# uInverter.net
KiCad netlist of a schematic drawn in Altium Designer
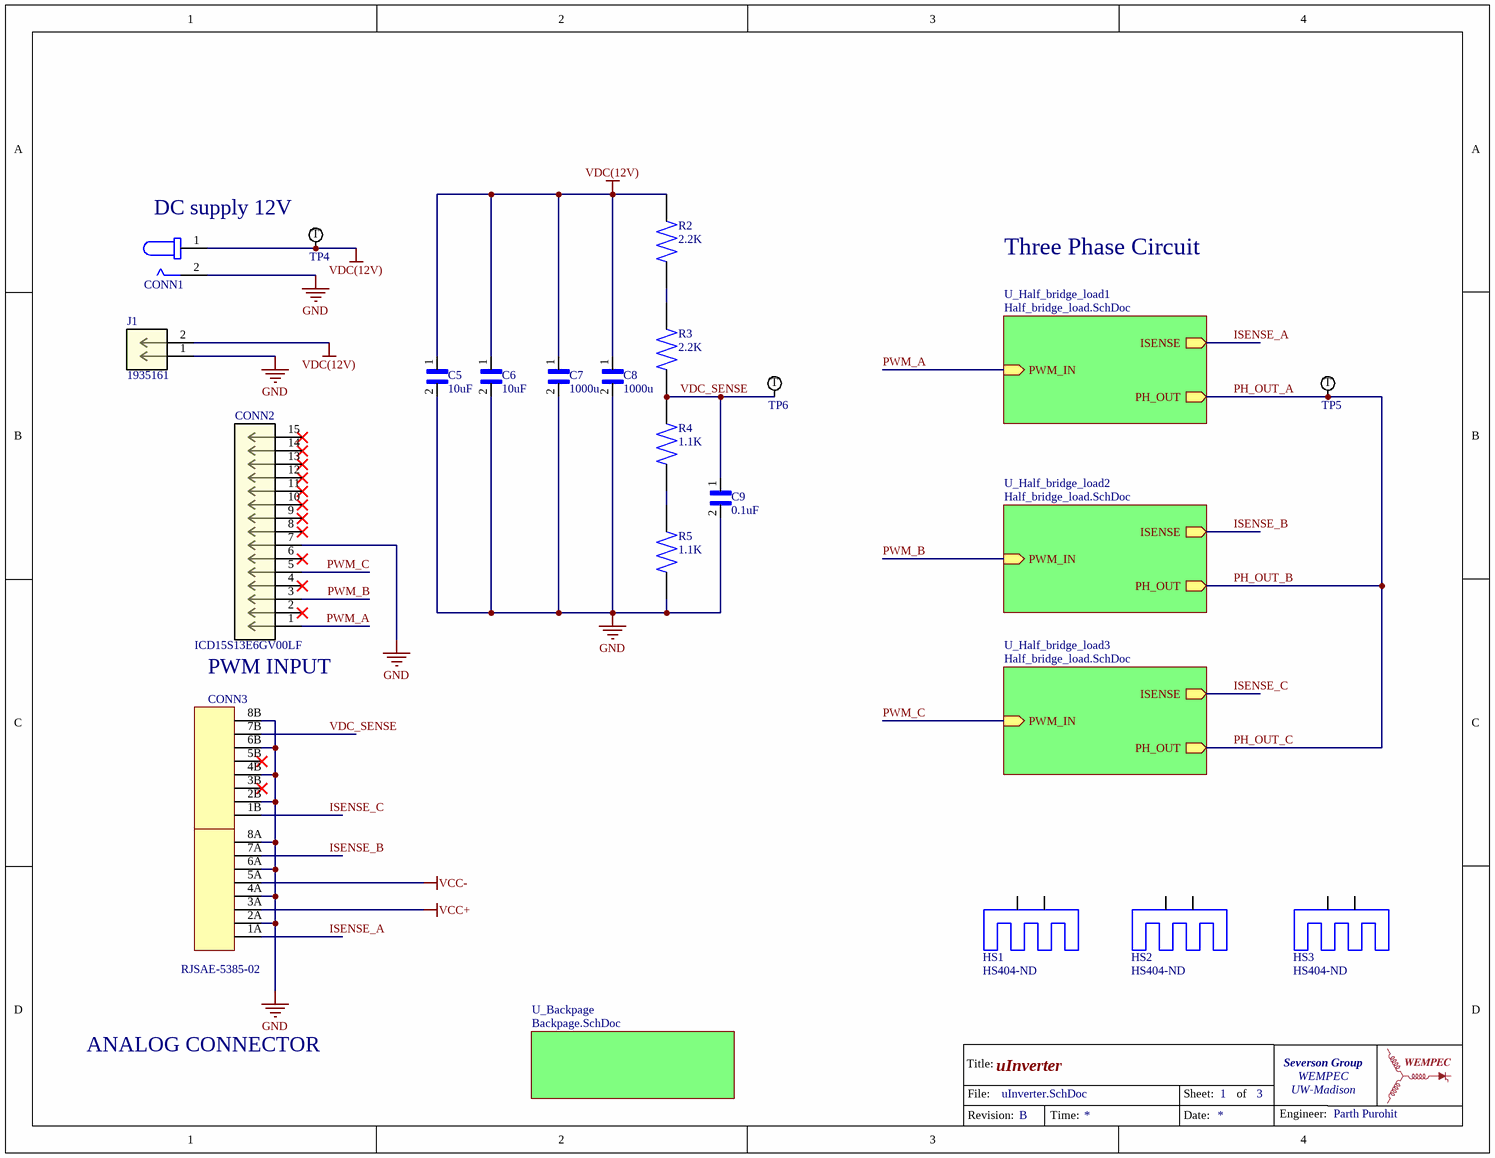
[diagram p0: uInverter.SchDoc]

(export (version "E")
  (design (tool "Eeschema 10.0.6"))
  (components
    (comp (ref "C5")
      (value "10uF")
      (footprint "PcbLib_uInverter:0805_CAP")
      (description "0805 35 V 10 uF ±10% Tolerance X5R Multilayer Ceramic Capacitor")
      (fields
        (field (name "MANUFACTURER") "Murata")
        (field (name "MANUFACTURER PART NUMBER") "GRM21BR6YA106KE43L")
      )
      (libsource (lib "Schlib_uInverter") (part "GRM21BR6YA106KE43L"))
    )
    (comp (ref "C6")
      (value "10uF")
      (footprint "PcbLib_uInverter:0805_CAP")
      (description "0805 35 V 10 uF ±10% Tolerance X5R Multilayer Ceramic Capacitor")
      (fields
        (field (name "MANUFACTURER") "Murata")
        (field (name "MANUFACTURER PART NUMBER") "GRM21BR6YA106KE43L")
      )
      (libsource (lib "Schlib_uInverter") (part "GRM21BR6YA106KE43L"))
    )
    (comp (ref "C7")
      (value "1000u")
      (footprint "CAP_PAN_12.5X25_PAN")
      (description "Cap Aluminum 1000uF 35V 20% (12.5 X 25mm) Radial 5mm 3190mA 7000 hr 105C Ammo Pack")
      (fields
        (field (name "MANUFACTURER") "Panasonic")
        (field (name "MANUFACTURER PART NUMBER") "EEU-FM1V102B")
      )
      (libsource (lib "Schlib_uInverter") (part "EEU-FM1V102B"))
    )
    (comp (ref "C8")
      (value "1000u")
      (footprint "CAP_PAN_12.5X25_PAN")
      (description "Cap Aluminum 1000uF 35V 20% (12.5 X 25mm) Radial 5mm 3190mA 7000 hr 105C Ammo Pack")
      (fields
        (field (name "MANUFACTURER") "Panasonic")
        (field (name "MANUFACTURER PART NUMBER") "EEU-FM1V102B")
      )
      (libsource (lib "Schlib_uInverter") (part "EEU-FM1V102B"))
    )
    (comp (ref "C9")
      (value "0.1uF")
      (footprint "PcbLib_uInverter:0805_CAP")
      (description "Capacitor 0.1uF 16V 0805 SMD X7R")
      (fields
        (field (name "MANUFACTURER") "Yageo")
        (field (name "MANUFACTURER PART NUMBER") "CC0805KRX7R7BB104")
      )
      (libsource (lib "Schlib_uInverter") (part "CC0805KRX7R7BB104"))
    )
    (comp (ref "CONN1")
      (value "PJ-037AH")
      (footprint "CUI_PJ-037AH")
      (description "CONN PWR JACK 2X5.5MM SOLDER")
      (fields (field (name "MANUFACTURER") "CUI"))
      (libsource (lib "Schlib_uInv01") (part "PJ-037AH"))
    )
    (comp (ref "CONN2")
      (value "ICD15S13E6GV00LF")
      (footprint "ICD15S13E6GV00LF")
      (description "Conn High Density D-Sub SKT 15 POS 2.28mm Solder RA Thru-Hole 15 Terminal 1 Port")
      (fields (field (name "MANUFACTURER") "Amphenol FCI"))
      (libsource (lib "Schlib_uInv01") (part "ICD15S13E6GV00LF"))
    )
    (comp (ref "CONN3")
      (value "RJSAE-5385-02")
      (footprint "CONN_RJSAE538502_AMP")
      (description "CONN MOD JACK 8P8C R/A SHIELDED")
      (fields (field (name "MANUFACTURER") "Amphenol Commercial"))
      (libsource (lib "Schlib_uInv01") (part "RJSAE-5385-02"))
    )
    (comp (ref "HS1")
      (value "529702B02500G")
      (footprint "530002")
      (description "Heat Sink Passive TO-220 Radial Thru-Hole 2.6C/W Black Anodized")
      (fields
        (field (name "MP") "530002B02500G")
        (field (name "MF") "Aavid Thermalloy")
        (field (name "SUPPLIER PART NUMBER 1") "HS404-ND")
      )
      (libsource (lib "Schlib_uInverter") (part "529702B02500G"))
    )
    (comp (ref "HS2")
      (value "529702B02500G")
      (footprint "530002")
      (description "Heat Sink Passive TO-220 Radial Thru-Hole 2.6C/W Black Anodized")
      (fields
        (field (name "MP") "530002B02500G")
        (field (name "MF") "Aavid Thermalloy")
        (field (name "SUPPLIER PART NUMBER 1") "HS404-ND")
      )
      (libsource (lib "Schlib_uInverter") (part "529702B02500G"))
    )
    (comp (ref "HS3")
      (value "529702B02500G")
      (footprint "530002")
      (description "Heat Sink Passive TO-220 Radial Thru-Hole 2.6C/W Black Anodized")
      (fields
        (field (name "MP") "530002B02500G")
        (field (name "MF") "Aavid Thermalloy")
        (field (name "SUPPLIER PART NUMBER 1") "HS404-ND")
      )
      (libsource (lib "Schlib_uInverter") (part "529702B02500G"))
    )
    (comp (ref "J1")
      (value "1935161")
      (footprint "PHOENIX_1935161")
      (description "Conn Terminal Blocks 2 POS 5mm Solder ST Thru-Hole 16A")
      (fields (field (name "MANUFACTURER") "Phoenix Contact") (field (name "VOLTAGE") "300V"))
      (libsource (lib "Schlib_uInv01") (part "1935161"))
    )
    (comp (ref "R2")
      (value "2.2K")
      (footprint "PcbLib_uInverter:0805_RES")
      (description "Res Thick Film 0805 2.2K Ohm 1% 0.4W")
      (fields
        (field (name "MANUFACTURER") "Vishay Dale")
        (field (name "MANUFACTURER PART NUMBER") "RCS08052K20FKEA")
      )
      (libsource (lib "Schlib_uInverter") (part "RCS08052K20FKEA"))
    )
    (comp (ref "R3")
      (value "2.2K")
      (footprint "PcbLib_uInverter:0805_RES")
      (description "Res Thick Film 0805 2.2K Ohm 1% 0.4W")
      (fields
        (field (name "MANUFACTURER") "Vishay Dale")
        (field (name "MANUFACTURER PART NUMBER") "RCS08052K20FKEA")
      )
      (libsource (lib "Schlib_uInverter") (part "RCS08052K20FKEA"))
    )
    (comp (ref "R4")
      (value "1.1K")
      (footprint "PcbLib_uInverter:0805_RES")
      (description "Res Thick Film 0805 1.1K Ohm 1% 0.4W")
      (fields (field (name "MANUFACTURER") "Rohm") (field (name "MANUFACTURER PART NUMBER") "ESR10EZPF1101"))
      (libsource (lib "Schlib_uInverter") (part "ESR10EZPF1101"))
    )
    (comp (ref "R5")
      (value "1.1K")
      (footprint "PcbLib_uInverter:0805_RES")
      (description "Res Thick Film 0805 1.1K Ohm 1% 0.4W")
      (fields (field (name "MANUFACTURER") "Rohm") (field (name "MANUFACTURER PART NUMBER") "ESR10EZPF1101"))
      (libsource (lib "Schlib_uInverter") (part "ESR10EZPF1101"))
    )
    (comp (ref "TitleBlockWEMPEC1")
      (value "TitleBlockWEMPEC")
      (libsource (lib "Schlib_uInv01") (part "TitleBlockWEMPEC"))
    )
    (comp (ref "TP4")
      (value "Test Point")
      (footprint "TP_1.6MM")
      (description "Conn Test Point SKT 1 POS ST Thru-Hole 1 Port")
      (fields
        (field (name "MANUFACTURER") "Keystone Electronics")
        (field (name "MANUFACTURER PART NUMBER") "5005")
      )
      (libsource (lib "Schlib_uInverter") (part "Test Point 36-5005ND"))
    )
    (comp (ref "TP5")
      (value "Test Point")
      (footprint "TP_1.6MM")
      (description "Conn Test Point SKT 1 POS ST Thru-Hole 1 Port")
      (fields
        (field (name "MANUFACTURER") "Keystone Electronics")
        (field (name "MANUFACTURER PART NUMBER") "5005")
      )
      (libsource (lib "Schlib_uInverter") (part "Test Point 36-5005ND"))
    )
    (comp (ref "TP6")
      (value "Test Point")
      (footprint "TP_1.6MM")
      (description "Conn Test Point SKT 1 POS ST Thru-Hole 1 Port")
      (fields
        (field (name "MANUFACTURER") "Keystone Electronics")
        (field (name "MANUFACTURER PART NUMBER") "5005")
      )
      (libsource (lib "Schlib_uInverter") (part "Test Point 36-5005ND"))
    )
  )
  (nets
    (net (code "1") (name "/ISENSE_A") (class "Default")
      (node (ref "CONN3") (pin "1A") (pinfunction "79_1A") (pintype "passive"))
    )
    (net (code "2") (name "/ISENSE_B") (class "Default")
      (node (ref "CONN3") (pin "7A") (pinfunction "79_7A") (pintype "passive"))
    )
    (net (code "3") (name "/ISENSE_C") (class "Default")
      (node (ref "CONN3") (pin "1B") (pinfunction "79_1B") (pintype "passive"))
    )
    (net (code "4") (name "/PH_OUT_A") (class "Default")
      (node (ref "TP5") (pin "1") (pinfunction "1_1") (pintype "passive"))
    )
    (net (code "5") (name "/PWM_A") (class "Default")
      (node (ref "CONN2") (pin "1") (pinfunction "1_1") (pintype "passive"))
    )
    (net (code "6") (name "/PWM_B") (class "Default")
      (node (ref "CONN2") (pin "3") (pinfunction "3_3") (pintype "passive"))
    )
    (net (code "7") (name "/PWM_C") (class "Default")
      (node (ref "CONN2") (pin "5") (pinfunction "5_5") (pintype "passive"))
    )
    (net (code "8") (name "/VDC_SENSE") (class "Default")
      (node (ref "C9") (pin "1") (pinfunction "1_1") (pintype "passive"))
      (node (ref "CONN3") (pin "7B") (pinfunction "79_7B") (pintype "passive"))
      (node (ref "R3") (pin "1") (pinfunction "1_1") (pintype "passive"))
      (node (ref "R4") (pin "2") (pinfunction "2_2") (pintype "passive"))
      (node (ref "TP6") (pin "1") (pinfunction "1_1") (pintype "passive"))
    )
    (net (code "9") (name "GND") (class "Default")
      (node (ref "C5") (pin "2") (pinfunction "2_2") (pintype "passive"))
      (node (ref "C6") (pin "2") (pinfunction "2_2") (pintype "passive"))
      (node (ref "C7") (pin "2") (pinfunction "2_2") (pintype "passive"))
      (node (ref "C8") (pin "2") (pinfunction "2_2") (pintype "passive"))
      (node (ref "C9") (pin "2") (pinfunction "2_2") (pintype "passive"))
      (node (ref "CONN1") (pin "2") (pinfunction "2_2") (pintype "passive"))
      (node (ref "CONN2") (pin "7") (pinfunction "7_7") (pintype "passive"))
      (node (ref "CONN3") (pin "2A") (pinfunction "79_2A") (pintype "passive"))
      (node (ref "CONN3") (pin "2B") (pinfunction "79_2B") (pintype "passive"))
      (node (ref "CONN3") (pin "4A") (pinfunction "79_4A") (pintype "passive"))
      (node (ref "CONN3") (pin "4B") (pinfunction "79_4B") (pintype "passive"))
      (node (ref "CONN3") (pin "6A") (pinfunction "79_6A") (pintype "passive"))
      (node (ref "CONN3") (pin "6B") (pinfunction "79_6B") (pintype "passive"))
      (node (ref "CONN3") (pin "8A") (pinfunction "79_8A") (pintype "passive"))
      (node (ref "CONN3") (pin "8B") (pinfunction "79_8B") (pintype "passive"))
      (node (ref "J1") (pin "1") (pinfunction "1_1") (pintype "passive"))
      (node (ref "R5") (pin "1") (pinfunction "1_1") (pintype "passive"))
    )
    (net (code "10") (name "Net-(R2-Pad1)") (class "Default")
      (node (ref "R2") (pin "1") (pinfunction "1_1") (pintype "passive"))
      (node (ref "R3") (pin "2") (pinfunction "2_2") (pintype "passive"))
    )
    (net (code "11") (name "Net-(R4-Pad1)") (class "Default")
      (node (ref "R4") (pin "1") (pinfunction "1_1") (pintype "passive"))
      (node (ref "R5") (pin "2") (pinfunction "2_2") (pintype "passive"))
    )
    (net (code "12") (name "VCC+") (class "Default")
      (node (ref "CONN3") (pin "3A") (pinfunction "79_3A") (pintype "passive"))
    )
    (net (code "13") (name "VCC-") (class "Default")
      (node (ref "CONN3") (pin "5A") (pinfunction "79_5A") (pintype "passive"))
    )
    (net (code "14") (name "VDC(12V)") (class "Default")
      (node (ref "C5") (pin "1") (pinfunction "1_1") (pintype "passive"))
      (node (ref "C6") (pin "1") (pinfunction "1_1") (pintype "passive"))
      (node (ref "C7") (pin "1") (pinfunction "1_1") (pintype "passive"))
      (node (ref "C8") (pin "1") (pinfunction "1_1") (pintype "passive"))
      (node (ref "CONN1") (pin "1") (pinfunction "1_1") (pintype "passive"))
      (node (ref "J1") (pin "2") (pinfunction "2_2") (pintype "passive"))
      (node (ref "R2") (pin "2") (pinfunction "2_2") (pintype "passive"))
      (node (ref "TP4") (pin "1") (pinfunction "1_1") (pintype "passive"))
    )
    (net (code "15") (name "unconnected-(CONN2-Pad2)") (class "Default")
      (node (ref "CONN2") (pin "2") (pinfunction "2_2") (pintype "passive+no_connect"))
    )
    (net (code "16") (name "unconnected-(CONN2-Pad4)") (class "Default")
      (node (ref "CONN2") (pin "4") (pinfunction "4_4") (pintype "passive+no_connect"))
    )
    (net (code "17") (name "unconnected-(CONN2-Pad6)") (class "Default")
      (node (ref "CONN2") (pin "6") (pinfunction "6_6") (pintype "passive+no_connect"))
    )
    (net (code "18") (name "unconnected-(CONN2-Pad8)") (class "Default")
      (node (ref "CONN2") (pin "8") (pinfunction "8_8") (pintype "passive+no_connect"))
    )
    (net (code "19") (name "unconnected-(CONN2-Pad9)") (class "Default")
      (node (ref "CONN2") (pin "9") (pinfunction "9_9") (pintype "passive+no_connect"))
    )
    (net (code "20") (name "unconnected-(CONN2-Pad10)") (class "Default")
      (node (ref "CONN2") (pin "10") (pinfunction "10_10") (pintype "passive+no_connect"))
    )
    (net (code "21") (name "unconnected-(CONN2-Pad11)") (class "Default")
      (node (ref "CONN2") (pin "11") (pinfunction "11_11") (pintype "passive+no_connect"))
    )
    (net (code "22") (name "unconnected-(CONN2-Pad12)") (class "Default")
      (node (ref "CONN2") (pin "12") (pinfunction "12_12") (pintype "passive+no_connect"))
    )
    (net (code "23") (name "unconnected-(CONN2-Pad13)") (class "Default")
      (node (ref "CONN2") (pin "13") (pinfunction "13_13") (pintype "passive+no_connect"))
    )
    (net (code "24") (name "unconnected-(CONN2-Pad14)") (class "Default")
      (node (ref "CONN2") (pin "14") (pinfunction "14_14") (pintype "passive+no_connect"))
    )
    (net (code "25") (name "unconnected-(CONN2-Pad15)") (class "Default")
      (node (ref "CONN2") (pin "15") (pinfunction "15_15") (pintype "passive+no_connect"))
    )
    (net (code "26") (name "unconnected-(CONN3-79-Pad3B)") (class "Default")
      (node (ref "CONN3") (pin "3B") (pinfunction "79_3B") (pintype "passive+no_connect"))
    )
    (net (code "27") (name "unconnected-(CONN3-79-Pad5B)") (class "Default")
      (node (ref "CONN3") (pin "5B") (pinfunction "79_5B") (pintype "passive+no_connect"))
    )
    (net (code "28") (name "unconnected-(HS1-1-PadP$1)") (class "Default")
      (node (ref "HS1") (pin "P$1") (pinfunction "1_P$1") (pintype "bidirectional"))
    )
    (net (code "29") (name "unconnected-(HS1-2-PadP$2)") (class "Default")
      (node (ref "HS1") (pin "P$2") (pinfunction "2_P$2") (pintype "bidirectional"))
    )
    (net (code "30") (name "unconnected-(HS2-1-PadP$1)") (class "Default")
      (node (ref "HS2") (pin "P$1") (pinfunction "1_P$1") (pintype "bidirectional"))
    )
    (net (code "31") (name "unconnected-(HS2-2-PadP$2)") (class "Default")
      (node (ref "HS2") (pin "P$2") (pinfunction "2_P$2") (pintype "bidirectional"))
    )
    (net (code "32") (name "unconnected-(HS3-1-PadP$1)") (class "Default")
      (node (ref "HS3") (pin "P$1") (pinfunction "1_P$1") (pintype "bidirectional"))
    )
    (net (code "33") (name "unconnected-(HS3-2-PadP$2)") (class "Default")
      (node (ref "HS3") (pin "P$2") (pinfunction "2_P$2") (pintype "bidirectional"))
    )
  )
)
